# ArticulatedPCBControlPower.net
KiCad netlist of a schematic drawn in EAGLE
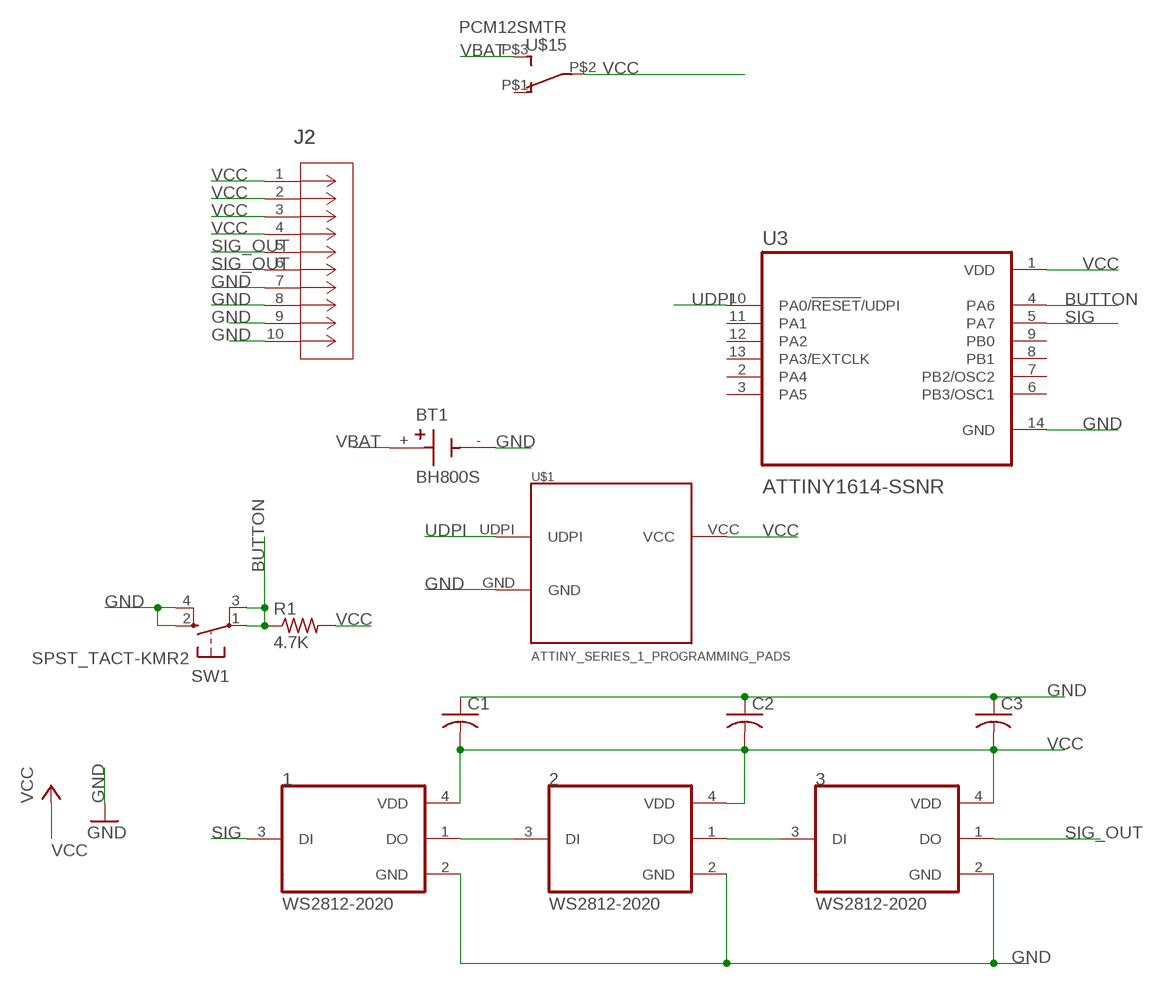
[diagram p0: schematic, sheet 1]

(export (version "E")
  (design (tool "Eeschema 10.0.6"))
  (components
    (comp (ref "1")
      (value "WS2812-2020")
      (footprint "eagle-import:LED_WS2812-2020")
      (fields (field (name "MF") "Worldsemi"))
      (libsource (lib "eagle-import") (part "WS2812-2020"))
    )
    (comp (ref "2")
      (value "WS2812-2020")
      (footprint "eagle-import:LED_WS2812-2020")
      (fields (field (name "MF") "Worldsemi"))
      (libsource (lib "eagle-import") (part "WS2812-2020"))
    )
    (comp (ref "3")
      (value "WS2812-2020")
      (footprint "eagle-import:LED_WS2812-2020")
      (fields (field (name "MF") "Worldsemi"))
      (libsource (lib "eagle-import") (part "WS2812-2020"))
    )
    (comp (ref "BT1")
      (value "BH800S")
      (footprint "eagle-import:BAT_BH800S")
      (fields (field (name "DIGI-KEY_PART_NUMBER") "BH800S-ABS-BULK-ND") (field (name "MF") "MPD"))
      (libsource (lib "eagle-import") (part "BH800S"))
    )
    (comp (ref "C1")
      (value "C-USC0603")
      (footprint "eagle-import:C0603")
      (libsource (lib "eagle-import") (part "C-USC0603"))
    )
    (comp (ref "C2")
      (value "C-USC0603")
      (footprint "eagle-import:C0603")
      (libsource (lib "eagle-import") (part "C-USC0603"))
    )
    (comp (ref "C3")
      (value "C-USC0603")
      (footprint "eagle-import:C0603")
      (libsource (lib "eagle-import") (part "C-USC0603"))
    )
    (comp (ref "J2")
      (value "DF23C-10DP-0.5V(92)")
      (footprint "eagle-import:CONN_DF23C-10DP-0.5V(92)_HIR")
      (fields (field (name "COPYRIGHT") "Copyright (C) 2018 Accelerated Designs. All rights reserved"))
      (libsource (lib "eagle-import") (part "DF23C-10DP-0.5V(92)"))
    )
    (comp (ref "R1")
      (value "4.7K")
      (footprint "eagle-import:R0603")
      (libsource (lib "eagle-import") (part "R-US_R0603"))
    )
    (comp (ref "SW1")
      (value "SPST_TACT-KMR2")
      (footprint "eagle-import:KMR2")
      (libsource (lib "eagle-import") (part "SPST_TACT-KMR2"))
    )
    (comp (ref "U$1")
      (value "ATTINY_SERIES_1_PROGRAMMING_PADS")
      (footprint "eagle-import:ATTINY_SERIES_1_PROGRAMMING_PADS")
      (libsource (lib "eagle-import") (part "ATTINY_SERIES_1_PROGRAMMING_PADS"))
    )
    (comp (ref "U$15")
      (value "PCM12SMTR")
      (footprint "eagle-import:PCM12SMTR")
      (libsource (lib "eagle-import") (part "PCM12SMTR"))
    )
    (comp (ref "U3")
      (value "ATTINY1614-SSNR")
      (footprint "eagle-import:SOIC127P600X175-14N")
      (fields (field (name "MF") "Microchip Technology"))
      (libsource (lib "eagle-import") (part "ATTINY1614-SSNR"))
    )
  )
  (nets
    (net (code "1") (name "/BUTTON") (class "Default")
      (node (ref "R1") (pin "1") (pinfunction "1_1") (pintype "passive"))
      (node (ref "SW1") (pin "1") (pinfunction "P_1") (pintype "passive"))
      (node (ref "SW1") (pin "3") (pinfunction "P1_3") (pintype "passive"))
      (node (ref "U3") (pin "4") (pinfunction "PA6_4") (pintype "bidirectional"))
    )
    (net (code "2") (name "/SIG") (class "Default")
      (node (ref "1") (pin "3") (pinfunction "DI_3") (pintype "input"))
      (node (ref "U3") (pin "5") (pinfunction "PA7_5") (pintype "bidirectional"))
    )
    (net (code "3") (name "/SIG_OUT") (class "Default")
      (node (ref "3") (pin "1") (pinfunction "DO_1") (pintype "output"))
      (node (ref "J2") (pin "5") (pinfunction "5_5") (pintype "passive"))
      (node (ref "J2") (pin "6") (pinfunction "6_6") (pintype "passive"))
    )
    (net (code "4") (name "/UDPI") (class "Default")
      (node (ref "U$1") (pin "UDPI") (pinfunction "UDPI_UDPI") (pintype "bidirectional"))
      (node (ref "U3") (pin "10") (pinfunction "PA0/~{RESET}/UDPI_10") (pintype "bidirectional"))
    )
    (net (code "5") (name "/VBAT") (class "Default")
      (node (ref "BT1") (pin "+") (pinfunction "+_+") (pintype "passive"))
      (node (ref "U$15") (pin "P$3") (pinfunction "3_P$3") (pintype "passive"))
    )
    (net (code "6") (name "GND") (class "Default")
      (node (ref "1") (pin "2") (pinfunction "GND_2") (pintype "power_in"))
      (node (ref "2") (pin "2") (pinfunction "GND_2") (pintype "power_in"))
      (node (ref "3") (pin "2") (pinfunction "GND_2") (pintype "power_in"))
      (node (ref "BT1") (pin "-") (pinfunction "-_-") (pintype "passive"))
      (node (ref "C1") (pin "1") (pinfunction "1_1") (pintype "passive"))
      (node (ref "C2") (pin "1") (pinfunction "1_1") (pintype "passive"))
      (node (ref "C3") (pin "1") (pinfunction "1_1") (pintype "passive"))
      (node (ref "J2") (pin "10") (pinfunction "10_10") (pintype "passive"))
      (node (ref "J2") (pin "7") (pinfunction "7_7") (pintype "passive"))
      (node (ref "J2") (pin "8") (pinfunction "8_8") (pintype "passive"))
      (node (ref "J2") (pin "9") (pinfunction "9_9") (pintype "passive"))
      (node (ref "SW1") (pin "2") (pinfunction "S_2") (pintype "passive"))
      (node (ref "SW1") (pin "4") (pinfunction "S1_4") (pintype "passive"))
      (node (ref "U$1") (pin "GND") (pinfunction "GND_GND") (pintype "bidirectional"))
      (node (ref "U3") (pin "14") (pinfunction "GND_14") (pintype "power_in"))
    )
    (net (code "7") (name "Net-(1-DO)") (class "Default")
      (node (ref "1") (pin "1") (pinfunction "DO_1") (pintype "output"))
      (node (ref "2") (pin "3") (pinfunction "DI_3") (pintype "input"))
    )
    (net (code "8") (name "Net-(2-DO)") (class "Default")
      (node (ref "2") (pin "1") (pinfunction "DO_1") (pintype "output"))
      (node (ref "3") (pin "3") (pinfunction "DI_3") (pintype "input"))
    )
    (net (code "9") (name "VCC") (class "Default")
      (node (ref "1") (pin "4") (pinfunction "VDD_4") (pintype "power_in"))
      (node (ref "2") (pin "4") (pinfunction "VDD_4") (pintype "power_in"))
      (node (ref "3") (pin "4") (pinfunction "VDD_4") (pintype "power_in"))
      (node (ref "C1") (pin "2") (pinfunction "2_2") (pintype "passive"))
      (node (ref "C2") (pin "2") (pinfunction "2_2") (pintype "passive"))
      (node (ref "C3") (pin "2") (pinfunction "2_2") (pintype "passive"))
      (node (ref "J2") (pin "1") (pinfunction "1_1") (pintype "passive"))
      (node (ref "J2") (pin "2") (pinfunction "2_2") (pintype "passive"))
      (node (ref "J2") (pin "3") (pinfunction "3_3") (pintype "passive"))
      (node (ref "J2") (pin "4") (pinfunction "4_4") (pintype "passive"))
      (node (ref "R1") (pin "2") (pinfunction "2_2") (pintype "passive"))
      (node (ref "U$1") (pin "VCC") (pinfunction "VCC_VCC") (pintype "bidirectional"))
      (node (ref "U$15") (pin "P$2") (pinfunction "2_P$2") (pintype "passive"))
      (node (ref "U3") (pin "1") (pinfunction "VDD_1") (pintype "power_in"))
    )
    (net (code "10") (name "unconnected-(U$15-1-PadP$1)") (class "Default")
      (node (ref "U$15") (pin "P$1") (pinfunction "1_P$1") (pintype "passive"))
    )
    (net (code "11") (name "unconnected-(U3-PA1-Pad11)") (class "Default")
      (node (ref "U3") (pin "11") (pinfunction "PA1_11") (pintype "bidirectional"))
    )
    (net (code "12") (name "unconnected-(U3-PA2-Pad12)") (class "Default")
      (node (ref "U3") (pin "12") (pinfunction "PA2_12") (pintype "bidirectional"))
    )
    (net (code "13") (name "unconnected-(U3-PA3{slash}EXTCLK-Pad13)") (class "Default")
      (node (ref "U3") (pin "13") (pinfunction "PA3/EXTCLK_13") (pintype "bidirectional"))
    )
    (net (code "14") (name "unconnected-(U3-PA4-Pad2)") (class "Default")
      (node (ref "U3") (pin "2") (pinfunction "PA4_2") (pintype "bidirectional"))
    )
    (net (code "15") (name "unconnected-(U3-PA5-Pad3)") (class "Default")
      (node (ref "U3") (pin "3") (pinfunction "PA5_3") (pintype "bidirectional"))
    )
    (net (code "16") (name "unconnected-(U3-PB0-Pad9)") (class "Default")
      (node (ref "U3") (pin "9") (pinfunction "PB0_9") (pintype "bidirectional"))
    )
    (net (code "17") (name "unconnected-(U3-PB1-Pad8)") (class "Default")
      (node (ref "U3") (pin "8") (pinfunction "PB1_8") (pintype "bidirectional"))
    )
    (net (code "18") (name "unconnected-(U3-PB2{slash}OSC2-Pad7)") (class "Default")
      (node (ref "U3") (pin "7") (pinfunction "PB2/OSC2_7") (pintype "bidirectional"))
    )
    (net (code "19") (name "unconnected-(U3-PB3{slash}OSC1-Pad6)") (class "Default")
      (node (ref "U3") (pin "6") (pinfunction "PB3/OSC1_6") (pintype "bidirectional"))
    )
  )
)
